# 11_Watchdog.net
KiCad netlist of a schematic drawn in Altium Designer
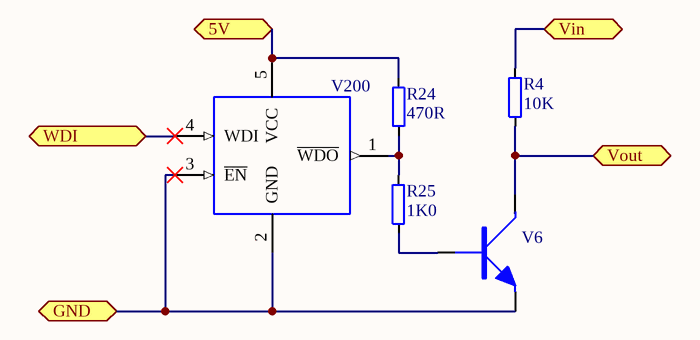
[diagram p0: 11_Watchdog.SchDoc]

(export (version "E")
  (design (tool "Eeschema 10.0.6"))
  (components
    (comp (ref "R4")
      (value "10K")
      (footprint "1206")
      (description "Resistor")
      (fields
        (field (name "MANUFACTURER") "Phycomp")
        (field (name "PARTNUMBER") "RC1206FR-0710KL")
        (field (name "CHECKEDBY") "ART")
      )
      (libsource (lib "SVN_BOMGEN_Database_2014") (part "RES"))
    )
    (comp (ref "R24")
      (value "470R")
      (footprint "1206")
      (description "Resistor")
      (fields
        (field (name "MANUFACTURER") "Phycomp")
        (field (name "PARTNUMBER") "RC1206FR-07470RL")
        (field (name "CHECKEDBY") "ART")
      )
      (libsource (lib "SVN_BOMGEN_Database_2014") (part "RES"))
    )
    (comp (ref "R25")
      (value "1K0")
      (footprint "1206")
      (description "Resistor")
      (fields
        (field (name "MANUFACTURER") "Phycomp")
        (field (name "PARTNUMBER") "RC1206FR-071KL")
        (field (name "CHECKEDBY") "ART")
      )
      (libsource (lib "SVN_BOMGEN_Database_2014") (part "RES"))
    )
    (comp (ref "V6")
      (value "BC846B")
      (footprint "SOT23")
      (description "NPN Transistor SOT23")
      (fields (field (name "MANUFACTURER") "NXP") (field (name "CHECKEDBY") "LZZ"))
      (libsource (lib "SVN_BOMGEN_Database_2014") (part "NPN-SOT23"))
    )
    (comp (ref "V200")
      (value "STWD100NYWY3F")
      (footprint "SOT23-5")
      (description "IC Watchdog Timer Circuit")
      (fields (field (name "MANUFACTURER") "ST Microelectronics") (field (name "CHECKEDBY") "SAA"))
      (libsource (lib "SVN_BOMGEN_Database_2014") (part "STWD100"))
    )
  )
  (nets
    (net (code "1") (name "/5V") (class "Default")
      (node (ref "R24") (pin "1") (pinfunction "1_1") (pintype "passive"))
      (node (ref "V200") (pin "5") (pinfunction "VCC_5") (pintype "power_in"))
    )
    (net (code "2") (name "/GND") (class "Default")
      (node (ref "V200") (pin "2") (pinfunction "GND_2") (pintype "power_in"))
      (node (ref "V200") (pin "3") (pinfunction "~{EN}_3") (pintype "input"))
      (node (ref "V6") (pin "y") (pinfunction "Emitter_y") (pintype "passive"))
    )
    (net (code "3") (name "/Vin") (class "Default")
      (node (ref "R4") (pin "2") (pinfunction "2_2") (pintype "passive"))
    )
    (net (code "4") (name "/Vout") (class "Default")
      (node (ref "R4") (pin "1") (pinfunction "1_1") (pintype "passive"))
      (node (ref "V6") (pin "x") (pinfunction "Collector_x") (pintype "passive"))
    )
    (net (code "5") (name "/WDI") (class "Default")
      (node (ref "V200") (pin "4") (pinfunction "WDI_4") (pintype "input+no_connect"))
    )
    (net (code "6") (name "Net-(V6-Base)") (class "Default")
      (node (ref "R25") (pin "1") (pinfunction "1_1") (pintype "passive"))
      (node (ref "V6") (pin "z") (pinfunction "Base_z") (pintype "passive"))
    )
    (net (code "7") (name "Net-(V200-~{WDO})") (class "Default")
      (node (ref "R24") (pin "2") (pinfunction "2_2") (pintype "passive"))
      (node (ref "R25") (pin "2") (pinfunction "2_2") (pintype "passive"))
      (node (ref "V200") (pin "1") (pinfunction "~{WDO}_1") (pintype "output"))
    )
  )
)
